# Microcontroller_board_Photodiode_plate.net
KiCad netlist of a schematic drawn in EasyEDA
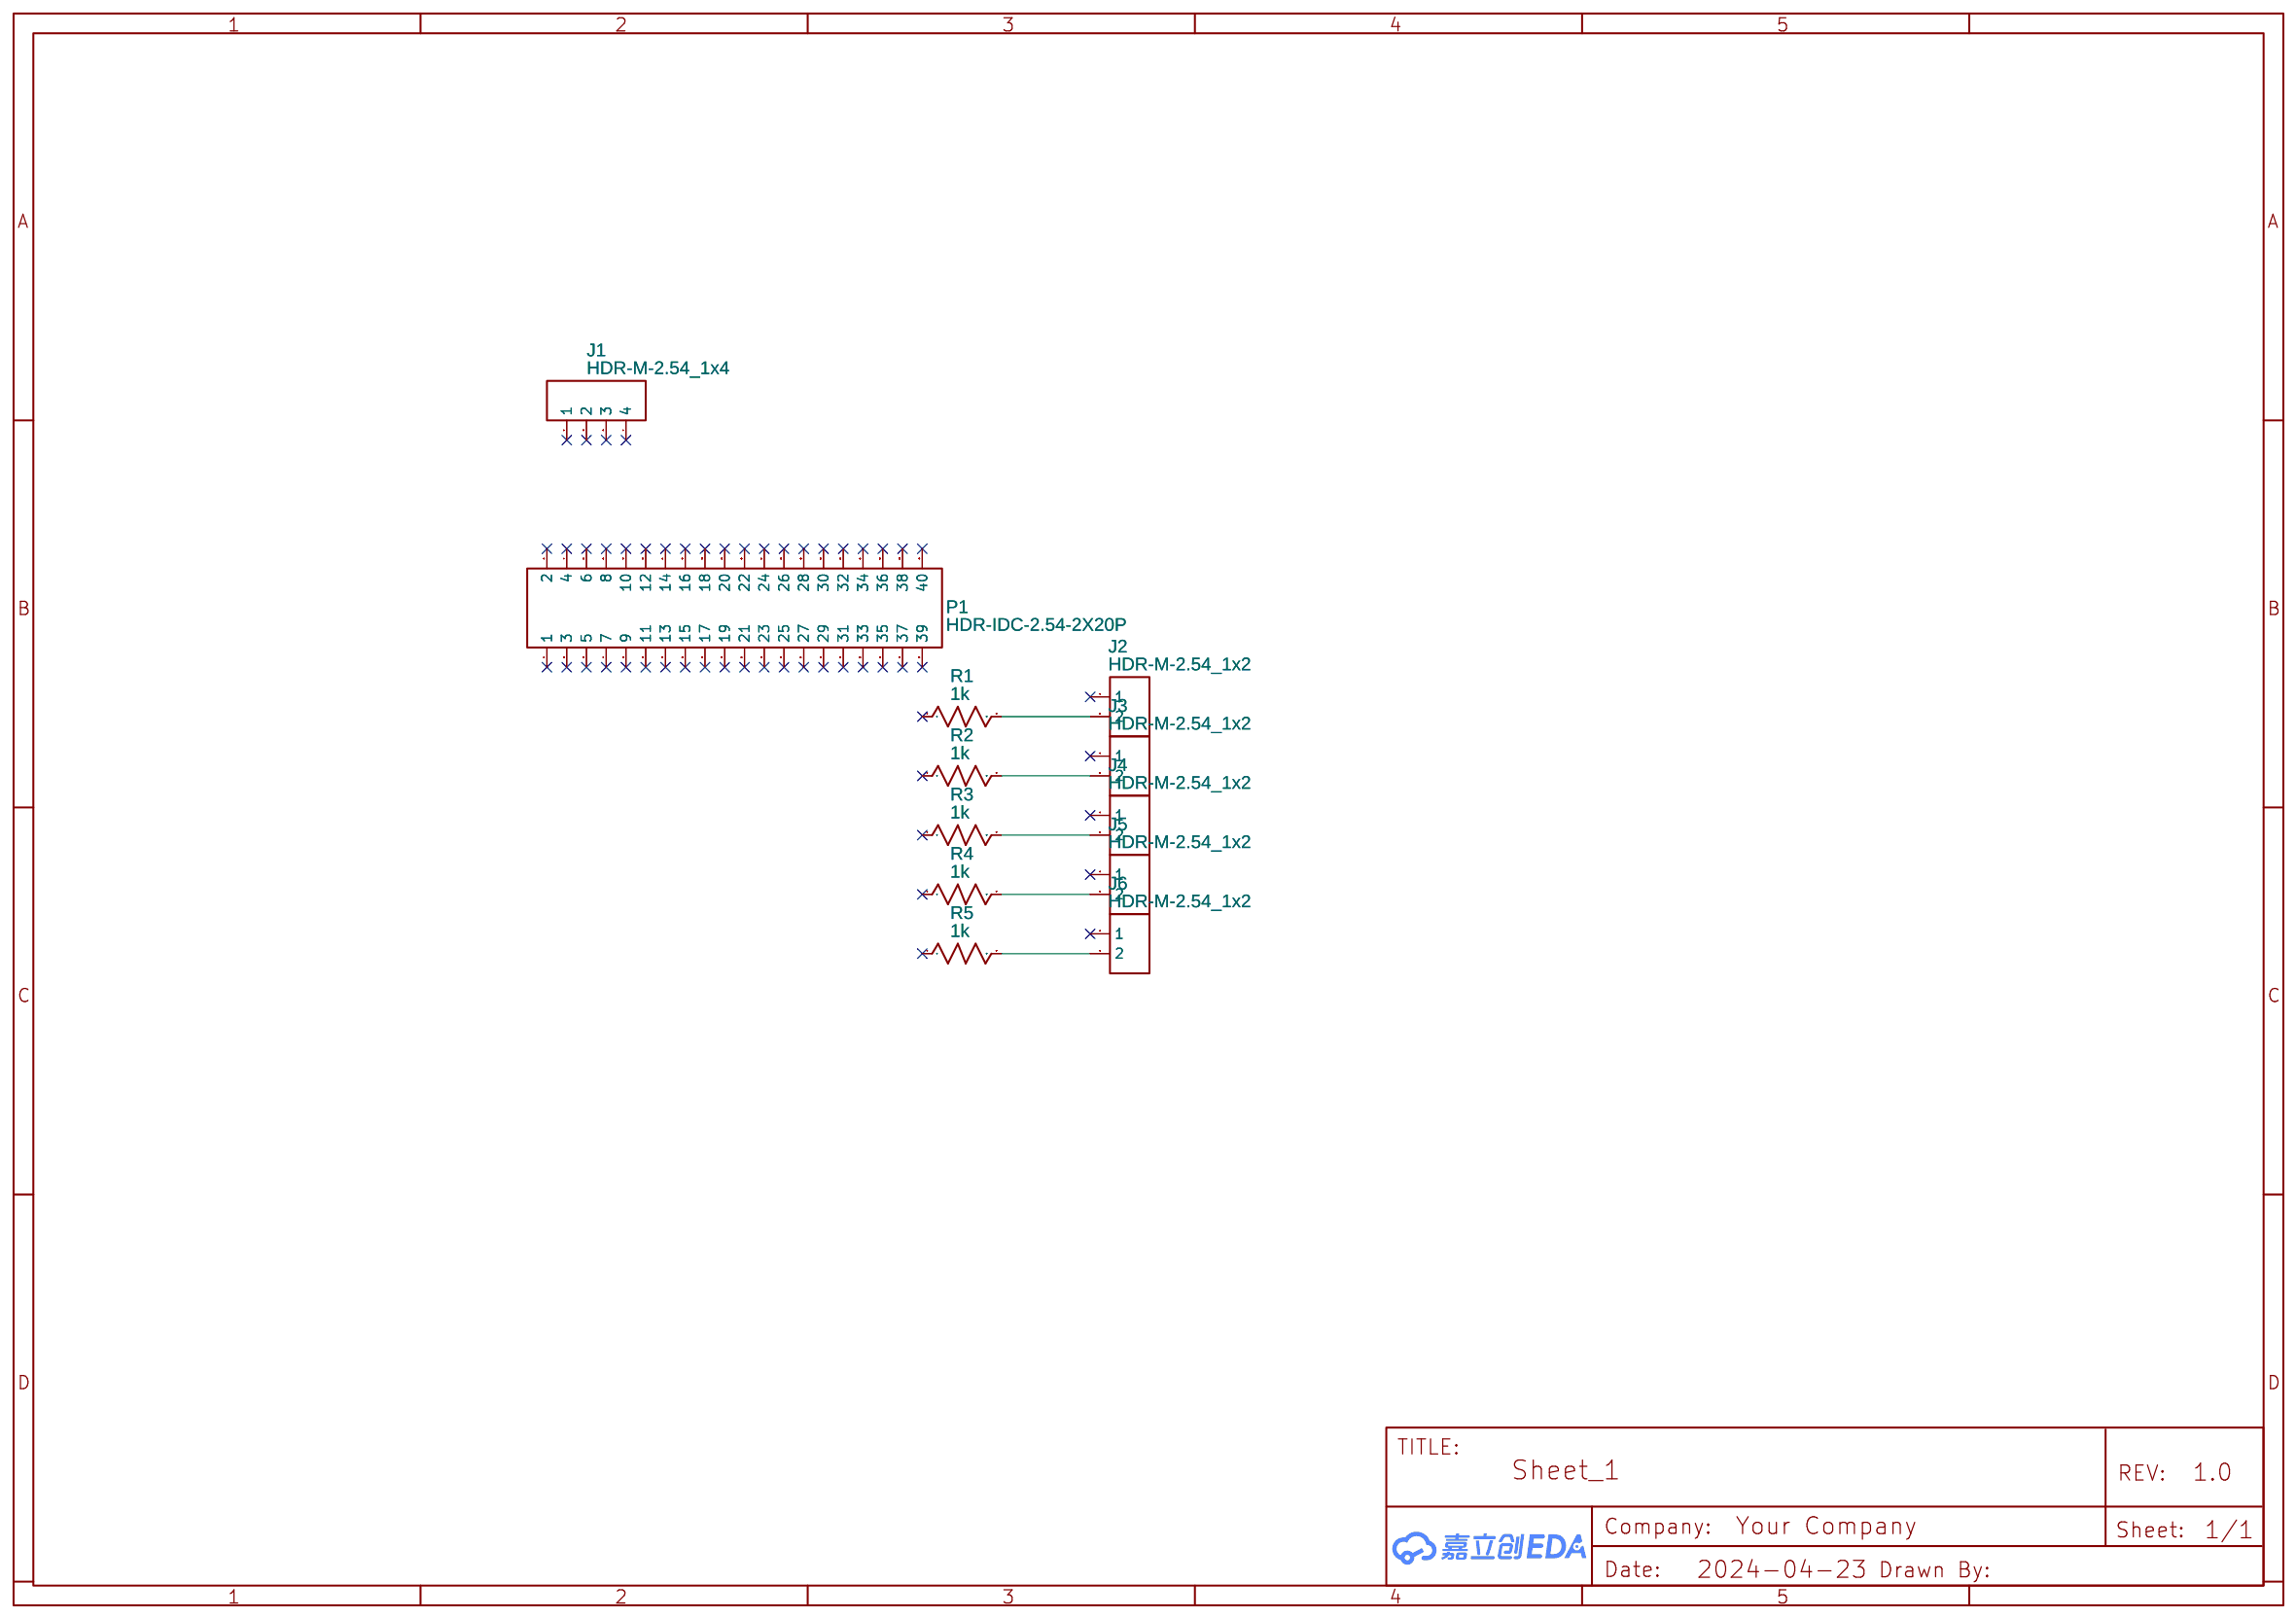
[diagram p0: schematic sheet]

(export (version "E")
  (design (tool "Eeschema 10.0.6"))
  (components
    (comp (ref "J1")
      (value "HDR-M-2.54_1x4")
      (fields (field (name "BOM_Supplier Part") "C124378"))
      (libsource (lib "") (part "HDR-M-2.54_1x4"))
    )
    (comp (ref "J2")
      (value "HDR-M-2.54_1x2")
      (fields (field (name "BOM_Supplier Part") "C124375"))
      (libsource (lib "") (part "HDR-M-2.54_1x2"))
    )
    (comp (ref "J3")
      (value "HDR-M-2.54_1x2")
      (fields (field (name "BOM_Supplier Part") "C124375"))
      (libsource (lib "") (part "HDR-M-2.54_1x2"))
    )
    (comp (ref "J4")
      (value "HDR-M-2.54_1x2")
      (fields (field (name "BOM_Supplier Part") "C124375"))
      (libsource (lib "") (part "HDR-M-2.54_1x2"))
    )
    (comp (ref "J5")
      (value "HDR-M-2.54_1x2")
      (fields (field (name "BOM_Supplier Part") "C124375"))
      (libsource (lib "") (part "HDR-M-2.54_1x2"))
    )
    (comp (ref "J6")
      (value "HDR-M-2.54_1x2")
      (fields (field (name "BOM_Supplier Part") "C124375"))
      (libsource (lib "") (part "HDR-M-2.54_1x2"))
    )
    (comp (ref "P1")
      (value "HDR-IDC-2.54-2X20P")
      (fields
        (field (name "BOM_Manufacturer Part") "IDC Box 2X20 2.54MM")
        (field (name "BOM_Supplier Part") "C9138")
      )
      (libsource (lib "") (part "HDR-IDC-2.54-2X20P"))
    )
    (comp (ref "R1") (value "1k") (libsource (lib "") (part "R_AXIAL-1.2_US")))
    (comp (ref "R2") (value "1k") (libsource (lib "") (part "R_AXIAL-1.2_US")))
    (comp (ref "R3") (value "1k") (libsource (lib "") (part "R_AXIAL-1.2_US")))
    (comp (ref "R4") (value "1k") (libsource (lib "") (part "R_AXIAL-1.2_US")))
    (comp (ref "R5") (value "1k") (libsource (lib "") (part "R_AXIAL-1.2_US")))
  )
  (nets
    (net (code "1") (name "Net-(J2-Pad2)") (class "Default")
      (node (ref "J2") (pin "2") (pinfunction "2_2") (pintype "unspecified"))
      (node (ref "R1") (pin "2") (pinfunction "2_2") (pintype "unspecified"))
    )
    (net (code "2") (name "Net-(J3-Pad2)") (class "Default")
      (node (ref "J3") (pin "2") (pinfunction "2_2") (pintype "unspecified"))
      (node (ref "R2") (pin "2") (pinfunction "2_2") (pintype "unspecified"))
    )
    (net (code "3") (name "Net-(J4-Pad2)") (class "Default")
      (node (ref "J4") (pin "2") (pinfunction "2_2") (pintype "unspecified"))
      (node (ref "R3") (pin "2") (pinfunction "2_2") (pintype "unspecified"))
    )
    (net (code "4") (name "Net-(J5-Pad2)") (class "Default")
      (node (ref "J5") (pin "2") (pinfunction "2_2") (pintype "unspecified"))
      (node (ref "R4") (pin "2") (pinfunction "2_2") (pintype "unspecified"))
    )
    (net (code "5") (name "Net-(J6-Pad2)") (class "Default")
      (node (ref "J6") (pin "2") (pinfunction "2_2") (pintype "unspecified"))
      (node (ref "R5") (pin "2") (pinfunction "2_2") (pintype "unspecified"))
    )
    (net (code "6") (name "unconnected-(J1-Pad1)") (class "Default")
      (node (ref "J1") (pin "1") (pinfunction "1_1") (pintype "unspecified+no_connect"))
    )
    (net (code "7") (name "unconnected-(J1-Pad2)") (class "Default")
      (node (ref "J1") (pin "2") (pinfunction "2_2") (pintype "unspecified+no_connect"))
    )
    (net (code "8") (name "unconnected-(J1-Pad3)") (class "Default")
      (node (ref "J1") (pin "3") (pinfunction "3_3") (pintype "unspecified+no_connect"))
    )
    (net (code "9") (name "unconnected-(J1-Pad4)") (class "Default")
      (node (ref "J1") (pin "4") (pinfunction "4_4") (pintype "unspecified+no_connect"))
    )
    (net (code "10") (name "unconnected-(J2-Pad1)") (class "Default")
      (node (ref "J2") (pin "1") (pinfunction "1_1") (pintype "unspecified+no_connect"))
    )
    (net (code "11") (name "unconnected-(J3-Pad1)") (class "Default")
      (node (ref "J3") (pin "1") (pinfunction "1_1") (pintype "unspecified+no_connect"))
    )
    (net (code "12") (name "unconnected-(J4-Pad1)") (class "Default")
      (node (ref "J4") (pin "1") (pinfunction "1_1") (pintype "unspecified+no_connect"))
    )
    (net (code "13") (name "unconnected-(J5-Pad1)") (class "Default")
      (node (ref "J5") (pin "1") (pinfunction "1_1") (pintype "unspecified+no_connect"))
    )
    (net (code "14") (name "unconnected-(J6-Pad1)") (class "Default")
      (node (ref "J6") (pin "1") (pinfunction "1_1") (pintype "unspecified+no_connect"))
    )
    (net (code "15") (name "unconnected-(P1-Pad1)") (class "Default")
      (node (ref "P1") (pin "1") (pinfunction "1_1") (pintype "unspecified+no_connect"))
    )
    (net (code "16") (name "unconnected-(P1-Pad2)") (class "Default")
      (node (ref "P1") (pin "2") (pinfunction "2_2") (pintype "unspecified+no_connect"))
    )
    (net (code "17") (name "unconnected-(P1-Pad3)") (class "Default")
      (node (ref "P1") (pin "3") (pinfunction "3_3") (pintype "unspecified+no_connect"))
    )
    (net (code "18") (name "unconnected-(P1-Pad4)") (class "Default")
      (node (ref "P1") (pin "4") (pinfunction "4_4") (pintype "unspecified+no_connect"))
    )
    (net (code "19") (name "unconnected-(P1-Pad5)") (class "Default")
      (node (ref "P1") (pin "5") (pinfunction "5_5") (pintype "unspecified+no_connect"))
    )
    (net (code "20") (name "unconnected-(P1-Pad6)") (class "Default")
      (node (ref "P1") (pin "6") (pinfunction "6_6") (pintype "unspecified+no_connect"))
    )
    (net (code "21") (name "unconnected-(P1-Pad7)") (class "Default")
      (node (ref "P1") (pin "7") (pinfunction "7_7") (pintype "unspecified+no_connect"))
    )
    (net (code "22") (name "unconnected-(P1-Pad8)") (class "Default")
      (node (ref "P1") (pin "8") (pinfunction "8_8") (pintype "unspecified+no_connect"))
    )
    (net (code "23") (name "unconnected-(P1-Pad9)") (class "Default")
      (node (ref "P1") (pin "9") (pinfunction "9_9") (pintype "unspecified+no_connect"))
    )
    (net (code "24") (name "unconnected-(P1-Pad10)") (class "Default")
      (node (ref "P1") (pin "10") (pinfunction "10_10") (pintype "unspecified+no_connect"))
    )
    (net (code "25") (name "unconnected-(P1-Pad11)") (class "Default")
      (node (ref "P1") (pin "11") (pinfunction "11_11") (pintype "unspecified+no_connect"))
    )
    (net (code "26") (name "unconnected-(P1-Pad12)") (class "Default")
      (node (ref "P1") (pin "12") (pinfunction "12_12") (pintype "unspecified+no_connect"))
    )
    (net (code "27") (name "unconnected-(P1-Pad13)") (class "Default")
      (node (ref "P1") (pin "13") (pinfunction "13_13") (pintype "unspecified+no_connect"))
    )
    (net (code "28") (name "unconnected-(P1-Pad14)") (class "Default")
      (node (ref "P1") (pin "14") (pinfunction "14_14") (pintype "unspecified+no_connect"))
    )
    (net (code "29") (name "unconnected-(P1-Pad15)") (class "Default")
      (node (ref "P1") (pin "15") (pinfunction "15_15") (pintype "unspecified+no_connect"))
    )
    (net (code "30") (name "unconnected-(P1-Pad16)") (class "Default")
      (node (ref "P1") (pin "16") (pinfunction "16_16") (pintype "unspecified+no_connect"))
    )
    (net (code "31") (name "unconnected-(P1-Pad17)") (class "Default")
      (node (ref "P1") (pin "17") (pinfunction "17_17") (pintype "unspecified+no_connect"))
    )
    (net (code "32") (name "unconnected-(P1-Pad18)") (class "Default")
      (node (ref "P1") (pin "18") (pinfunction "18_18") (pintype "unspecified+no_connect"))
    )
    (net (code "33") (name "unconnected-(P1-Pad19)") (class "Default")
      (node (ref "P1") (pin "19") (pinfunction "19_19") (pintype "unspecified+no_connect"))
    )
    (net (code "34") (name "unconnected-(P1-Pad20)") (class "Default")
      (node (ref "P1") (pin "20") (pinfunction "20_20") (pintype "unspecified+no_connect"))
    )
    (net (code "35") (name "unconnected-(P1-Pad21)") (class "Default")
      (node (ref "P1") (pin "21") (pinfunction "21_21") (pintype "unspecified+no_connect"))
    )
    (net (code "36") (name "unconnected-(P1-Pad22)") (class "Default")
      (node (ref "P1") (pin "22") (pinfunction "22_22") (pintype "unspecified+no_connect"))
    )
    (net (code "37") (name "unconnected-(P1-Pad23)") (class "Default")
      (node (ref "P1") (pin "23") (pinfunction "23_23") (pintype "unspecified+no_connect"))
    )
    (net (code "38") (name "unconnected-(P1-Pad24)") (class "Default")
      (node (ref "P1") (pin "24") (pinfunction "24_24") (pintype "unspecified+no_connect"))
    )
    (net (code "39") (name "unconnected-(P1-Pad25)") (class "Default")
      (node (ref "P1") (pin "25") (pinfunction "25_25") (pintype "unspecified+no_connect"))
    )
    (net (code "40") (name "unconnected-(P1-Pad26)") (class "Default")
      (node (ref "P1") (pin "26") (pinfunction "26_26") (pintype "unspecified+no_connect"))
    )
    (net (code "41") (name "unconnected-(P1-Pad27)") (class "Default")
      (node (ref "P1") (pin "27") (pinfunction "27_27") (pintype "unspecified+no_connect"))
    )
    (net (code "42") (name "unconnected-(P1-Pad28)") (class "Default")
      (node (ref "P1") (pin "28") (pinfunction "28_28") (pintype "unspecified+no_connect"))
    )
    (net (code "43") (name "unconnected-(P1-Pad29)") (class "Default")
      (node (ref "P1") (pin "29") (pinfunction "29_29") (pintype "unspecified+no_connect"))
    )
    (net (code "44") (name "unconnected-(P1-Pad30)") (class "Default")
      (node (ref "P1") (pin "30") (pinfunction "30_30") (pintype "unspecified+no_connect"))
    )
    (net (code "45") (name "unconnected-(P1-Pad31)") (class "Default")
      (node (ref "P1") (pin "31") (pinfunction "31_31") (pintype "unspecified+no_connect"))
    )
    (net (code "46") (name "unconnected-(P1-Pad32)") (class "Default")
      (node (ref "P1") (pin "32") (pinfunction "32_32") (pintype "unspecified+no_connect"))
    )
    (net (code "47") (name "unconnected-(P1-Pad33)") (class "Default")
      (node (ref "P1") (pin "33") (pinfunction "33_33") (pintype "unspecified+no_connect"))
    )
    (net (code "48") (name "unconnected-(P1-Pad34)") (class "Default")
      (node (ref "P1") (pin "34") (pinfunction "34_34") (pintype "unspecified+no_connect"))
    )
    (net (code "49") (name "unconnected-(P1-Pad35)") (class "Default")
      (node (ref "P1") (pin "35") (pinfunction "35_35") (pintype "unspecified+no_connect"))
    )
    (net (code "50") (name "unconnected-(P1-Pad36)") (class "Default")
      (node (ref "P1") (pin "36") (pinfunction "36_36") (pintype "unspecified+no_connect"))
    )
    (net (code "51") (name "unconnected-(P1-Pad37)") (class "Default")
      (node (ref "P1") (pin "37") (pinfunction "37_37") (pintype "unspecified+no_connect"))
    )
    (net (code "52") (name "unconnected-(P1-Pad38)") (class "Default")
      (node (ref "P1") (pin "38") (pinfunction "38_38") (pintype "unspecified+no_connect"))
    )
    (net (code "53") (name "unconnected-(P1-Pad39)") (class "Default")
      (node (ref "P1") (pin "39") (pinfunction "39_39") (pintype "unspecified+no_connect"))
    )
    (net (code "54") (name "unconnected-(P1-Pad40)") (class "Default")
      (node (ref "P1") (pin "40") (pinfunction "40_40") (pintype "unspecified+no_connect"))
    )
    (net (code "55") (name "unconnected-(R1-Pad1)") (class "Default")
      (node (ref "R1") (pin "1") (pinfunction "1_1") (pintype "unspecified+no_connect"))
    )
    (net (code "56") (name "unconnected-(R2-Pad1)") (class "Default")
      (node (ref "R2") (pin "1") (pinfunction "1_1") (pintype "unspecified+no_connect"))
    )
    (net (code "57") (name "unconnected-(R3-Pad1)") (class "Default")
      (node (ref "R3") (pin "1") (pinfunction "1_1") (pintype "unspecified+no_connect"))
    )
    (net (code "58") (name "unconnected-(R4-Pad1)") (class "Default")
      (node (ref "R4") (pin "1") (pinfunction "1_1") (pintype "unspecified+no_connect"))
    )
    (net (code "59") (name "unconnected-(R5-Pad1)") (class "Default")
      (node (ref "R5") (pin "1") (pinfunction "1_1") (pintype "unspecified+no_connect"))
    )
  )
)
